# NFC.net
KiCad netlist of a schematic drawn in Altium Designer
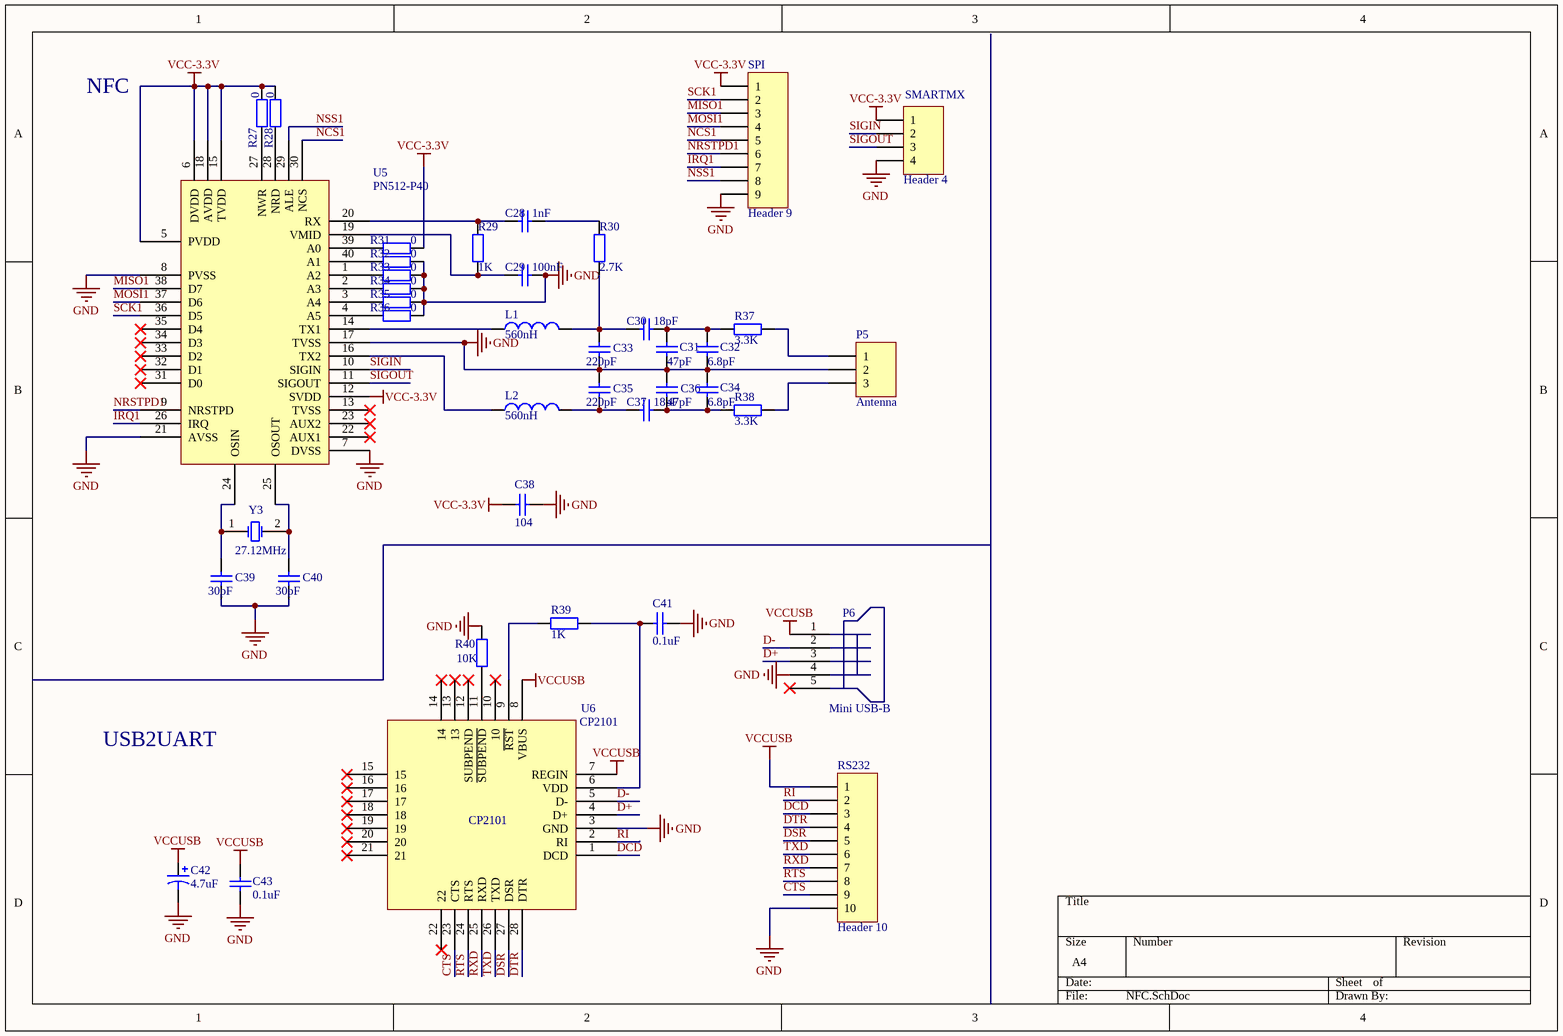
[diagram p0: NFC.SchDoc]

(export (version "E")
  (design (tool "Eeschema 10.0.6"))
  (components
    (comp (ref "C28")
      (value "1nF")
      (footprint "1608[0603]")
      (description "Capacitor")
      (fields (field (name "Comment") "Cap") (field (name "PUBLISHER") "Altium Limited"))
      (libsource (lib "common") (part "Cap"))
    )
    (comp (ref "C29")
      (value "100nF")
      (footprint "1608[0603]")
      (description "Capacitor")
      (fields (field (name "Comment") "Cap") (field (name "PUBLISHER") "Altium Limited"))
      (libsource (lib "common") (part "Cap"))
    )
    (comp (ref "C30")
      (value "18pF")
      (footprint "1608[0603]")
      (description "Capacitor")
      (fields (field (name "Comment") "Cap") (field (name "PUBLISHER") "Altium Limited"))
      (libsource (lib "common") (part "Cap"))
    )
    (comp (ref "C31")
      (value "47pF")
      (footprint "1608[0603]")
      (description "Capacitor")
      (fields (field (name "Comment") "Cap") (field (name "PUBLISHER") "Altium Limited"))
      (libsource (lib "common") (part "Cap"))
    )
    (comp (ref "C32")
      (value "6.8pF")
      (footprint "1608[0603]")
      (description "Capacitor")
      (fields (field (name "Comment") "Cap") (field (name "PUBLISHER") "Altium Limited"))
      (libsource (lib "common") (part "Cap"))
    )
    (comp (ref "C33")
      (value "220pF")
      (footprint "1608[0603]")
      (description "Capacitor")
      (fields (field (name "Comment") "Cap") (field (name "PUBLISHER") "Altium Limited"))
      (libsource (lib "common") (part "Cap"))
    )
    (comp (ref "C34")
      (value "6.8pF")
      (footprint "1608[0603]")
      (description "Capacitor")
      (fields (field (name "Comment") "Cap") (field (name "PUBLISHER") "Altium Limited"))
      (libsource (lib "common") (part "Cap"))
    )
    (comp (ref "C35")
      (value "220pF")
      (footprint "1608[0603]")
      (description "Capacitor")
      (fields (field (name "Comment") "Cap") (field (name "PUBLISHER") "Altium Limited"))
      (libsource (lib "common") (part "Cap"))
    )
    (comp (ref "C36")
      (value "47pF")
      (footprint "1608[0603]")
      (description "Capacitor")
      (fields (field (name "Comment") "Cap") (field (name "PUBLISHER") "Altium Limited"))
      (libsource (lib "common") (part "Cap"))
    )
    (comp (ref "C37")
      (value "18pF")
      (footprint "1608[0603]")
      (description "Capacitor")
      (fields (field (name "Comment") "Cap") (field (name "PUBLISHER") "Altium Limited"))
      (libsource (lib "common") (part "Cap"))
    )
    (comp (ref "C38")
      (value "104")
      (footprint "1608[0603]")
      (description "Capacitor")
      (fields (field (name "Comment") "Cap") (field (name "PUBLISHER") "Altium Limited"))
      (libsource (lib "common") (part "Cap"))
    )
    (comp (ref "C39")
      (value "30pF")
      (footprint "1608[0603]")
      (description "Capacitor")
      (fields (field (name "Comment") "Cap") (field (name "PUBLISHER") "Altium Limited"))
      (libsource (lib "common") (part "Cap"))
    )
    (comp (ref "C40")
      (value "30pF")
      (footprint "1608[0603]")
      (description "Capacitor")
      (fields (field (name "Comment") "Cap") (field (name "PUBLISHER") "Altium Limited"))
      (libsource (lib "common") (part "Cap"))
    )
    (comp (ref "C41")
      (value "0.1uF")
      (footprint "1608[0603]")
      (description "Capacitor")
      (fields (field (name "Comment") "Cap") (field (name "PUBLISHER") "Altium Limited"))
      (libsource (lib "common") (part "Cap"))
    )
    (comp (ref "C42")
      (value "4.7uF")
      (footprint "2012[0805] - POL")
      (description "Polarized Capacitor (Axial)")
      (fields (field (name "Comment") "CAP POL") (field (name "PUBLISHER") "Altium Limited"))
      (libsource (lib "common") (part "CAP POL"))
    )
    (comp (ref "C43")
      (value "0.1uF")
      (footprint "1608[0603]")
      (description "Capacitor")
      (fields (field (name "Comment") "Cap") (field (name "PUBLISHER") "Altium Limited"))
      (libsource (lib "common") (part "Cap"))
    )
    (comp (ref "L1")
      (value "560nH")
      (footprint "0402-A")
      (description "Inductor")
      (fields (field (name "PUBLISHER") "Altium Limited"))
      (libsource (lib "Miscellaneous Devices") (part "Inductor"))
    )
    (comp (ref "L2")
      (value "560nH")
      (footprint "0402-A")
      (description "Inductor")
      (fields (field (name "PUBLISHER") "Altium Limited"))
      (libsource (lib "Miscellaneous Devices") (part "Inductor"))
    )
    (comp (ref "P5")
      (value "Antenna")
      (footprint "HDR1X3")
      (description "Header, 3-Pin")
      (fields (field (name "PUBLISHER") "Altium Limited"))
      (libsource (lib "Miscellaneous Connectors") (part "Header 3"))
    )
    (comp (ref "P6")
      (value "Mini USB-B")
      (footprint "MINI USB-501")
      (description "Mini USB Type B")
      (libsource (lib "USB2UART") (part "USB"))
    )
    (comp (ref "R27")
      (value "0")
      (footprint "1608[0603]")
      (description "Resistor")
      (fields (field (name "Comment") "RES") (field (name "PUBLISHER") "Altium Limited"))
      (libsource (lib "") (part "RES_1"))
    )
    (comp (ref "R28")
      (value "0")
      (footprint "1608[0603]")
      (description "Resistor")
      (fields (field (name "Comment") "RES") (field (name "PUBLISHER") "Altium Limited"))
      (libsource (lib "") (part "RES_1"))
    )
    (comp (ref "R29")
      (value "1K")
      (footprint "1608[0603]")
      (description "Resistor")
      (fields (field (name "Comment") "RES") (field (name "PUBLISHER") "Altium Limited"))
      (libsource (lib "") (part "RES_1"))
    )
    (comp (ref "R30")
      (value "2.7K")
      (footprint "1608[0603]")
      (description "Resistor")
      (fields (field (name "Comment") "RES") (field (name "PUBLISHER") "Altium Limited"))
      (libsource (lib "") (part "RES_1"))
    )
    (comp (ref "R31")
      (value "0")
      (footprint "1608[0603]")
      (description "Resistor")
      (fields (field (name "Comment") "RES") (field (name "PUBLISHER") "Altium Limited"))
      (libsource (lib "common") (part "RES"))
    )
    (comp (ref "R32")
      (value "0")
      (footprint "1608[0603]")
      (description "Resistor")
      (fields (field (name "Comment") "RES") (field (name "PUBLISHER") "Altium Limited"))
      (libsource (lib "common") (part "RES"))
    )
    (comp (ref "R33")
      (value "0")
      (footprint "1608[0603]")
      (description "Resistor")
      (fields (field (name "Comment") "RES") (field (name "PUBLISHER") "Altium Limited"))
      (libsource (lib "common") (part "RES"))
    )
    (comp (ref "R34")
      (value "0")
      (footprint "1608[0603]")
      (description "Resistor")
      (fields (field (name "Comment") "RES") (field (name "PUBLISHER") "Altium Limited"))
      (libsource (lib "common") (part "RES"))
    )
    (comp (ref "R35")
      (value "0")
      (footprint "1608[0603]")
      (description "Resistor")
      (fields (field (name "Comment") "RES") (field (name "PUBLISHER") "Altium Limited"))
      (libsource (lib "common") (part "RES"))
    )
    (comp (ref "R36")
      (value "0")
      (footprint "1608[0603]")
      (description "Resistor")
      (fields (field (name "Comment") "RES") (field (name "PUBLISHER") "Altium Limited"))
      (libsource (lib "common") (part "RES"))
    )
    (comp (ref "R37")
      (value "3.3K")
      (footprint "1608[0603]")
      (description "Resistor")
      (fields (field (name "Comment") "RES") (field (name "PUBLISHER") "Altium Limited"))
      (libsource (lib "common") (part "RES"))
    )
    (comp (ref "R38")
      (value "3.3K")
      (footprint "1608[0603]")
      (description "Resistor")
      (fields (field (name "Comment") "RES") (field (name "PUBLISHER") "Altium Limited"))
      (libsource (lib "common") (part "RES"))
    )
    (comp (ref "R39")
      (value "1K")
      (footprint "1608[0603]")
      (description "Resistor")
      (fields (field (name "Comment") "Res") (field (name "PUBLISHER") "Altium Limited"))
      (libsource (lib "common") (part "RES"))
    )
    (comp (ref "R40")
      (value "10K")
      (footprint "1608[0603]")
      (description "Resistor")
      (fields (field (name "Comment") "Res") (field (name "PUBLISHER") "Altium Limited"))
      (libsource (lib "") (part "RES_1"))
    )
    (comp (ref "RS232")
      (value "Header 10")
      (footprint "HDR1X10")
      (description "Header, 10-Pin")
      (fields (field (name "PUBLISHER") "Altium Limited"))
      (libsource (lib "Miscellaneous Connectors") (part "Header 10"))
    )
    (comp (ref "SMARTMX")
      (value "Header 4")
      (footprint "HDR1X4")
      (description "Header, 4-Pin")
      (fields (field (name "PUBLISHER") "Altium Limited"))
      (libsource (lib "Miscellaneous Connectors") (part "Header 4"))
    )
    (comp (ref "SPI")
      (value "Header 9")
      (footprint "HDR1X9")
      (description "Header, 9-Pin")
      (fields (field (name "PUBLISHER") "Altium Limited"))
      (libsource (lib "Miscellaneous Connectors") (part "Header 9"))
    )
    (comp (ref "U5")
      (value "PN512-P40")
      (footprint "QFN50P600X600-40VN")
      (libsource (lib "*") (part "PN511-P40"))
    )
    (comp (ref "U6")
      (value "CP2101")
      (footprint "QFN50P500X500-28VAN")
      (libsource (lib "USB2UART") (part "CP2101"))
    )
    (comp (ref "Y3")
      (value "27.12MHz")
      (footprint "XTAL")
      (description "Crystal Oscillator")
      (fields (field (name "PUBLISHER") "Altium Limited"))
      (libsource (lib "common") (part "XTAL"))
    )
  )
  (nets
    (net (code "1") (name "/CTS") (class "Default")
      (node (ref "RS232") (pin "9") (pinfunction "9_9") (pintype "passive"))
      (node (ref "U6") (pin "23") (pinfunction "CTS_23") (pintype "passive"))
    )
    (net (code "2") (name "/D+") (class "Default")
      (node (ref "P6") (pin "3") (pinfunction "3_3") (pintype "passive"))
      (node (ref "U6") (pin "4") (pinfunction "D+_4") (pintype "passive"))
    )
    (net (code "3") (name "/D-") (class "Default")
      (node (ref "P6") (pin "2") (pinfunction "2_2") (pintype "passive"))
      (node (ref "U6") (pin "5") (pinfunction "D-_5") (pintype "passive"))
    )
    (net (code "4") (name "/DCD") (class "Default")
      (node (ref "RS232") (pin "3") (pinfunction "3_3") (pintype "passive"))
      (node (ref "U6") (pin "1") (pinfunction "DCD_1") (pintype "passive"))
    )
    (net (code "5") (name "/DSR") (class "Default")
      (node (ref "RS232") (pin "5") (pinfunction "5_5") (pintype "passive"))
      (node (ref "U6") (pin "27") (pinfunction "DSR_27") (pintype "passive"))
    )
    (net (code "6") (name "/DTR") (class "Default")
      (node (ref "RS232") (pin "4") (pinfunction "4_4") (pintype "passive"))
      (node (ref "U6") (pin "28") (pinfunction "DTR_28") (pintype "passive"))
    )
    (net (code "7") (name "/IRQ1") (class "Default")
      (node (ref "SPI") (pin "7") (pinfunction "7_7") (pintype "passive"))
      (node (ref "U5") (pin "26") (pinfunction "IRQ_26") (pintype "passive"))
    )
    (net (code "8") (name "/MISO1") (class "Default")
      (node (ref "SPI") (pin "3") (pinfunction "3_3") (pintype "passive"))
      (node (ref "U5") (pin "38") (pinfunction "D7_38") (pintype "passive"))
    )
    (net (code "9") (name "/MOSI1") (class "Default")
      (node (ref "SPI") (pin "4") (pinfunction "4_4") (pintype "passive"))
      (node (ref "U5") (pin "37") (pinfunction "D6_37") (pintype "passive"))
    )
    (net (code "10") (name "/NCS1") (class "Default")
      (node (ref "SPI") (pin "5") (pinfunction "5_5") (pintype "passive"))
      (node (ref "U5") (pin "30") (pinfunction "NCS_30") (pintype "passive"))
    )
    (net (code "11") (name "/NRSTPD1") (class "Default")
      (node (ref "SPI") (pin "6") (pinfunction "6_6") (pintype "passive"))
      (node (ref "U5") (pin "9") (pinfunction "NRSTPD_9") (pintype "passive"))
    )
    (net (code "12") (name "/NSS1") (class "Default")
      (node (ref "SPI") (pin "8") (pinfunction "8_8") (pintype "passive"))
      (node (ref "U5") (pin "29") (pinfunction "ALE_29") (pintype "passive"))
    )
    (net (code "13") (name "/RI") (class "Default")
      (node (ref "RS232") (pin "2") (pinfunction "2_2") (pintype "passive"))
      (node (ref "U6") (pin "2") (pinfunction "RI_2") (pintype "passive"))
    )
    (net (code "14") (name "/RTS") (class "Default")
      (node (ref "RS232") (pin "8") (pinfunction "8_8") (pintype "passive"))
      (node (ref "U6") (pin "24") (pinfunction "RTS_24") (pintype "passive"))
    )
    (net (code "15") (name "/RXD") (class "Default")
      (node (ref "RS232") (pin "7") (pinfunction "7_7") (pintype "passive"))
      (node (ref "U6") (pin "25") (pinfunction "RXD_25") (pintype "passive"))
    )
    (net (code "16") (name "/SCK1") (class "Default")
      (node (ref "SPI") (pin "2") (pinfunction "2_2") (pintype "passive"))
      (node (ref "U5") (pin "36") (pinfunction "D5_36") (pintype "passive"))
    )
    (net (code "17") (name "/SIGIN") (class "Default")
      (node (ref "SMARTMX") (pin "2") (pinfunction "2_2") (pintype "passive"))
      (node (ref "U5") (pin "10") (pinfunction "SIGIN_10") (pintype "passive"))
    )
    (net (code "18") (name "/SIGOUT") (class "Default")
      (node (ref "SMARTMX") (pin "3") (pinfunction "3_3") (pintype "passive"))
      (node (ref "U5") (pin "11") (pinfunction "SIGOUT_11") (pintype "passive"))
    )
    (net (code "19") (name "/TXD") (class "Default")
      (node (ref "RS232") (pin "6") (pinfunction "6_6") (pintype "passive"))
      (node (ref "U6") (pin "26") (pinfunction "TXD_26") (pintype "passive"))
    )
    (net (code "20") (name "GND") (class "Default")
      (node (ref "C29") (pin "2") (pinfunction "2_2") (pintype "passive"))
      (node (ref "C31") (pin "1") (pinfunction "1_1") (pintype "passive"))
      (node (ref "C32") (pin "1") (pinfunction "1_1") (pintype "passive"))
      (node (ref "C33") (pin "1") (pinfunction "1_1") (pintype "passive"))
      (node (ref "C34") (pin "2") (pinfunction "2_2") (pintype "passive"))
      (node (ref "C35") (pin "2") (pinfunction "2_2") (pintype "passive"))
      (node (ref "C36") (pin "2") (pinfunction "2_2") (pintype "passive"))
      (node (ref "C38") (pin "1") (pinfunction "1_1") (pintype "passive"))
      (node (ref "C39") (pin "1") (pinfunction "1_1") (pintype "passive"))
      (node (ref "C40") (pin "1") (pinfunction "1_1") (pintype "passive"))
      (node (ref "C41") (pin "1") (pinfunction "1_1") (pintype "passive"))
      (node (ref "C42") (pin "2") (pinfunction "2_2") (pintype "passive"))
      (node (ref "C43") (pin "1") (pinfunction "1_1") (pintype "passive"))
      (node (ref "P5") (pin "2") (pinfunction "2_2") (pintype "passive"))
      (node (ref "P6") (pin "4") (pinfunction "4_4") (pintype "passive"))
      (node (ref "R32") (pin "1") (pinfunction "1_1") (pintype "passive"))
      (node (ref "R33") (pin "1") (pinfunction "1_1") (pintype "passive"))
      (node (ref "R34") (pin "1") (pinfunction "1_1") (pintype "passive"))
      (node (ref "R35") (pin "1") (pinfunction "1_1") (pintype "passive"))
      (node (ref "R36") (pin "1") (pinfunction "1_1") (pintype "passive"))
      (node (ref "R40") (pin "2") (pinfunction "2_2") (pintype "passive"))
      (node (ref "RS232") (pin "10") (pinfunction "10_10") (pintype "passive"))
      (node (ref "SMARTMX") (pin "4") (pinfunction "4_4") (pintype "passive"))
      (node (ref "SPI") (pin "9") (pinfunction "9_9") (pintype "passive"))
      (node (ref "U5") (pin "17") (pinfunction "TVSS_17") (pintype "passive"))
      (node (ref "U5") (pin "21") (pinfunction "AVSS_21") (pintype "passive"))
      (node (ref "U5") (pin "7") (pinfunction "DVSS_7") (pintype "passive"))
      (node (ref "U5") (pin "8") (pinfunction "PVSS_8") (pintype "passive"))
      (node (ref "U6") (pin "3") (pinfunction "GND_3") (pintype "passive"))
    )
    (net (code "21") (name "Net-(C28-Pad2)") (class "Default")
      (node (ref "C28") (pin "2") (pinfunction "2_2") (pintype "passive"))
      (node (ref "R30") (pin "2") (pinfunction "2_2") (pintype "passive"))
    )
    (net (code "22") (name "Net-(C30-Pad1)") (class "Default")
      (node (ref "C30") (pin "1") (pinfunction "1_1") (pintype "passive"))
      (node (ref "C33") (pin "2") (pinfunction "2_2") (pintype "passive"))
      (node (ref "L1") (pin "2") (pinfunction "2_2") (pintype "passive"))
      (node (ref "R30") (pin "1") (pinfunction "1_1") (pintype "passive"))
    )
    (net (code "23") (name "Net-(C30-Pad2)") (class "Default")
      (node (ref "C30") (pin "2") (pinfunction "2_2") (pintype "passive"))
      (node (ref "C31") (pin "2") (pinfunction "2_2") (pintype "passive"))
      (node (ref "C32") (pin "2") (pinfunction "2_2") (pintype "passive"))
      (node (ref "R37") (pin "2") (pinfunction "2_2") (pintype "passive"))
    )
    (net (code "24") (name "Net-(C34-Pad1)") (class "Default")
      (node (ref "C34") (pin "1") (pinfunction "1_1") (pintype "passive"))
      (node (ref "C36") (pin "1") (pinfunction "1_1") (pintype "passive"))
      (node (ref "C37") (pin "2") (pinfunction "2_2") (pintype "passive"))
      (node (ref "R38") (pin "2") (pinfunction "2_2") (pintype "passive"))
    )
    (net (code "25") (name "Net-(C35-Pad1)") (class "Default")
      (node (ref "C35") (pin "1") (pinfunction "1_1") (pintype "passive"))
      (node (ref "C37") (pin "1") (pinfunction "1_1") (pintype "passive"))
      (node (ref "L2") (pin "2") (pinfunction "2_2") (pintype "passive"))
    )
    (net (code "26") (name "Net-(P5-Pad1)") (class "Default")
      (node (ref "P5") (pin "1") (pinfunction "1_1") (pintype "passive"))
      (node (ref "R37") (pin "1") (pinfunction "1_1") (pintype "passive"))
    )
    (net (code "27") (name "Net-(P5-Pad3)") (class "Default")
      (node (ref "P5") (pin "3") (pinfunction "3_3") (pintype "passive"))
      (node (ref "R38") (pin "1") (pinfunction "1_1") (pintype "passive"))
    )
    (net (code "28") (name "Net-(U5-A0)") (class "Default")
      (node (ref "R31") (pin "2") (pinfunction "2_2") (pintype "passive"))
      (node (ref "U5") (pin "39") (pinfunction "A0_39") (pintype "passive"))
    )
    (net (code "29") (name "Net-(U5-A1)") (class "Default")
      (node (ref "R32") (pin "2") (pinfunction "2_2") (pintype "passive"))
      (node (ref "U5") (pin "40") (pinfunction "A1_40") (pintype "passive"))
    )
    (net (code "30") (name "Net-(U5-A2)") (class "Default")
      (node (ref "R33") (pin "2") (pinfunction "2_2") (pintype "passive"))
      (node (ref "U5") (pin "1") (pinfunction "A2_1") (pintype "passive"))
    )
    (net (code "31") (name "Net-(U5-A3)") (class "Default")
      (node (ref "R34") (pin "2") (pinfunction "2_2") (pintype "passive"))
      (node (ref "U5") (pin "2") (pinfunction "A3_2") (pintype "passive"))
    )
    (net (code "32") (name "Net-(U5-A4)") (class "Default")
      (node (ref "R35") (pin "2") (pinfunction "2_2") (pintype "passive"))
      (node (ref "U5") (pin "3") (pinfunction "A4_3") (pintype "passive"))
    )
    (net (code "33") (name "Net-(U5-A5)") (class "Default")
      (node (ref "R36") (pin "2") (pinfunction "2_2") (pintype "passive"))
      (node (ref "U5") (pin "4") (pinfunction "A5_4") (pintype "passive"))
    )
    (net (code "34") (name "Net-(U5-NRD)") (class "Default")
      (node (ref "R28") (pin "1") (pinfunction "1_1") (pintype "passive"))
      (node (ref "U5") (pin "28") (pinfunction "NRD_28") (pintype "passive"))
    )
    (net (code "35") (name "Net-(U5-NWR)") (class "Default")
      (node (ref "R27") (pin "1") (pinfunction "1_1") (pintype "passive"))
      (node (ref "U5") (pin "27") (pinfunction "NWR_27") (pintype "passive"))
    )
    (net (code "36") (name "Net-(U5-OSIN)") (class "Default")
      (node (ref "C39") (pin "2") (pinfunction "2_2") (pintype "passive"))
      (node (ref "U5") (pin "24") (pinfunction "OSIN_24") (pintype "passive"))
      (node (ref "Y3") (pin "1") (pinfunction "OSC1_1") (pintype "passive"))
    )
    (net (code "37") (name "Net-(U5-OSOUT)") (class "Default")
      (node (ref "C40") (pin "2") (pinfunction "2_2") (pintype "passive"))
      (node (ref "U5") (pin "25") (pinfunction "OSOUT_25") (pintype "passive"))
      (node (ref "Y3") (pin "2") (pinfunction "OSC2_2") (pintype "passive"))
    )
    (net (code "38") (name "Net-(U5-RX)") (class "Default")
      (node (ref "C28") (pin "1") (pinfunction "1_1") (pintype "passive"))
      (node (ref "R29") (pin "2") (pinfunction "2_2") (pintype "passive"))
      (node (ref "U5") (pin "20") (pinfunction "RX_20") (pintype "passive"))
    )
    (net (code "39") (name "Net-(U5-TX1)") (class "Default")
      (node (ref "L1") (pin "1") (pinfunction "1_1") (pintype "passive"))
      (node (ref "U5") (pin "14") (pinfunction "TX1_14") (pintype "passive"))
    )
    (net (code "40") (name "Net-(U5-TX2)") (class "Default")
      (node (ref "L2") (pin "1") (pinfunction "1_1") (pintype "passive"))
      (node (ref "U5") (pin "16") (pinfunction "TX2_16") (pintype "passive"))
    )
    (net (code "41") (name "Net-(U5-VMID)") (class "Default")
      (node (ref "C29") (pin "1") (pinfunction "1_1") (pintype "passive"))
      (node (ref "R29") (pin "1") (pinfunction "1_1") (pintype "passive"))
      (node (ref "U5") (pin "19") (pinfunction "VMID_19") (pintype "passive"))
    )
    (net (code "42") (name "Net-(U6-VDD)") (class "Default")
      (node (ref "C41") (pin "2") (pinfunction "2_2") (pintype "passive"))
      (node (ref "R39") (pin "1") (pinfunction "1_1") (pintype "passive"))
      (node (ref "U6") (pin "6") (pinfunction "VDD_6") (pintype "passive"))
    )
    (net (code "43") (name "Net-(U6-~{RST})") (class "Default")
      (node (ref "R39") (pin "2") (pinfunction "2_2") (pintype "passive"))
      (node (ref "U6") (pin "9") (pinfunction "~{RST}_9") (pintype "passive"))
    )
    (net (code "44") (name "Net-(U6-~{SUBPEND})") (class "Default")
      (node (ref "R40") (pin "1") (pinfunction "1_1") (pintype "passive"))
      (node (ref "U6") (pin "11") (pinfunction "~{SUBPEND}_11") (pintype "passive"))
    )
    (net (code "45") (name "VCC-3.3V") (class "Default")
      (node (ref "C38") (pin "2") (pinfunction "2_2") (pintype "passive"))
      (node (ref "R27") (pin "2") (pinfunction "2_2") (pintype "passive"))
      (node (ref "R28") (pin "2") (pinfunction "2_2") (pintype "passive"))
      (node (ref "R31") (pin "1") (pinfunction "1_1") (pintype "passive"))
      (node (ref "SMARTMX") (pin "1") (pinfunction "1_1") (pintype "passive"))
      (node (ref "SPI") (pin "1") (pinfunction "1_1") (pintype "passive"))
      (node (ref "U5") (pin "12") (pinfunction "SVDD_12") (pintype "passive"))
      (node (ref "U5") (pin "15") (pinfunction "TVDD_15") (pintype "passive"))
      (node (ref "U5") (pin "18") (pinfunction "AVDD_18") (pintype "passive"))
      (node (ref "U5") (pin "5") (pinfunction "PVDD_5") (pintype "passive"))
      (node (ref "U5") (pin "6") (pinfunction "DVDD_6") (pintype "passive"))
    )
    (net (code "46") (name "VCCUSB") (class "Default")
      (node (ref "C42") (pin "1") (pinfunction "1_1") (pintype "passive"))
      (node (ref "C43") (pin "2") (pinfunction "2_2") (pintype "passive"))
      (node (ref "P6") (pin "1") (pinfunction "1_1") (pintype "passive"))
      (node (ref "RS232") (pin "1") (pinfunction "1_1") (pintype "passive"))
      (node (ref "U6") (pin "7") (pinfunction "REGIN_7") (pintype "passive"))
      (node (ref "U6") (pin "8") (pinfunction "VBUS_8") (pintype "passive"))
    )
    (net (code "47") (name "unconnected-(P6-Pad5)") (class "Default")
      (node (ref "P6") (pin "5") (pinfunction "5_5") (pintype "passive+no_connect"))
    )
    (net (code "48") (name "unconnected-(U5-AUX1-Pad22)") (class "Default")
      (node (ref "U5") (pin "22") (pinfunction "AUX1_22") (pintype "passive+no_connect"))
    )
    (net (code "49") (name "unconnected-(U5-AUX2-Pad23)") (class "Default")
      (node (ref "U5") (pin "23") (pinfunction "AUX2_23") (pintype "passive+no_connect"))
    )
    (net (code "50") (name "unconnected-(U5-D0-Pad31)") (class "Default")
      (node (ref "U5") (pin "31") (pinfunction "D0_31") (pintype "passive+no_connect"))
    )
    (net (code "51") (name "unconnected-(U5-D1-Pad32)") (class "Default")
      (node (ref "U5") (pin "32") (pinfunction "D1_32") (pintype "passive+no_connect"))
    )
    (net (code "52") (name "unconnected-(U5-D2-Pad33)") (class "Default")
      (node (ref "U5") (pin "33") (pinfunction "D2_33") (pintype "passive+no_connect"))
    )
    (net (code "53") (name "unconnected-(U5-D3-Pad34)") (class "Default")
      (node (ref "U5") (pin "34") (pinfunction "D3_34") (pintype "passive+no_connect"))
    )
    (net (code "54") (name "unconnected-(U5-D4-Pad35)") (class "Default")
      (node (ref "U5") (pin "35") (pinfunction "D4_35") (pintype "passive+no_connect"))
    )
    (net (code "55") (name "unconnected-(U5-TVSS-Pad13)") (class "Default")
      (node (ref "U5") (pin "13") (pinfunction "TVSS_13") (pintype "passive+no_connect"))
    )
    (net (code "56") (name "unconnected-(U6-Pad10)") (class "Default")
      (node (ref "U6") (pin "10") (pinfunction "10_10") (pintype "passive+no_connect"))
    )
    (net (code "57") (name "unconnected-(U6-Pad13)") (class "Default")
      (node (ref "U6") (pin "13") (pinfunction "13_13") (pintype "passive+no_connect"))
    )
    (net (code "58") (name "unconnected-(U6-Pad14)") (class "Default")
      (node (ref "U6") (pin "14") (pinfunction "14_14") (pintype "passive+no_connect"))
    )
    (net (code "59") (name "unconnected-(U6-Pad15)") (class "Default")
      (node (ref "U6") (pin "15") (pinfunction "15_15") (pintype "passive+no_connect"))
    )
    (net (code "60") (name "unconnected-(U6-Pad16)") (class "Default")
      (node (ref "U6") (pin "16") (pinfunction "16_16") (pintype "passive+no_connect"))
    )
    (net (code "61") (name "unconnected-(U6-Pad17)") (class "Default")
      (node (ref "U6") (pin "17") (pinfunction "17_17") (pintype "passive+no_connect"))
    )
    (net (code "62") (name "unconnected-(U6-Pad18)") (class "Default")
      (node (ref "U6") (pin "18") (pinfunction "18_18") (pintype "passive+no_connect"))
    )
    (net (code "63") (name "unconnected-(U6-Pad19)") (class "Default")
      (node (ref "U6") (pin "19") (pinfunction "19_19") (pintype "passive+no_connect"))
    )
    (net (code "64") (name "unconnected-(U6-Pad20)") (class "Default")
      (node (ref "U6") (pin "20") (pinfunction "20_20") (pintype "passive+no_connect"))
    )
    (net (code "65") (name "unconnected-(U6-Pad21)") (class "Default")
      (node (ref "U6") (pin "21") (pinfunction "21_21") (pintype "passive+no_connect"))
    )
    (net (code "66") (name "unconnected-(U6-Pad22)") (class "Default")
      (node (ref "U6") (pin "22") (pinfunction "22_22") (pintype "passive+no_connect"))
    )
    (net (code "67") (name "unconnected-(U6-SUBPEND-Pad12)") (class "Default")
      (node (ref "U6") (pin "12") (pinfunction "SUBPEND_12") (pintype "passive+no_connect"))
    )
  )
)
